# module_led.net
KiCad netlist of a schematic drawn in Altium Designer
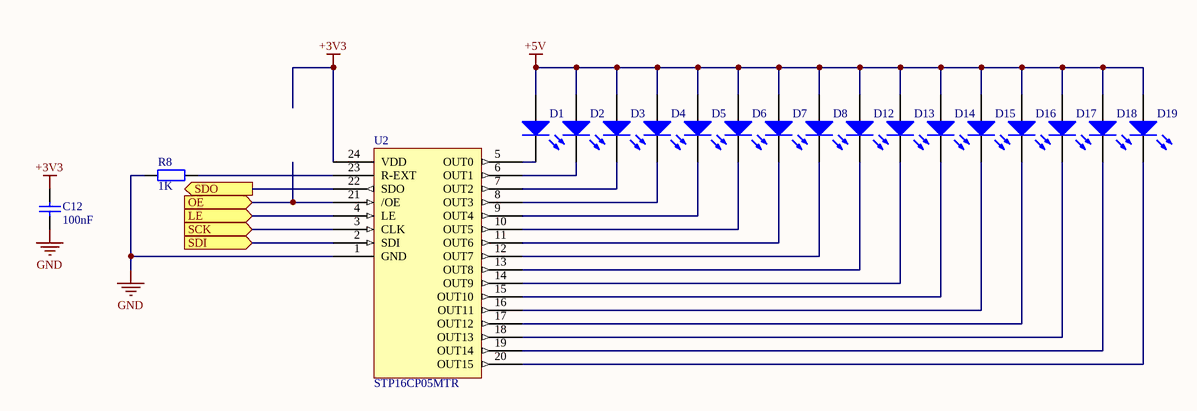
[diagram p0: module_led.SchDoc]

(export (version "E")
  (design (tool "Eeschema 10.0.6"))
  (components
    (comp (ref "C12")
      (value "100nF")
      (footprint "FP_0805_CAP_085")
      (description "Capacitor")
      (fields (field (name "VOLTAGE") "50V"))
      (libsource (lib "hallglib-2018") (part "CAP 100nF"))
    )
    (comp (ref "D1")
      (value "LED")
      (footprint "FP_0805_LED_RED")
      (description "Typical RED GaAs LED")
      (libsource (lib "hallglib") (part "LED"))
    )
    (comp (ref "D2")
      (value "LED")
      (footprint "FP_0805_LED_RED")
      (description "Typical RED GaAs LED")
      (libsource (lib "hallglib") (part "LED"))
    )
    (comp (ref "D3")
      (value "LED")
      (footprint "FP_0805_LED_RED")
      (description "Typical RED GaAs LED")
      (libsource (lib "hallglib") (part "LED"))
    )
    (comp (ref "D4")
      (value "LED")
      (footprint "FP_0805_LED_RED")
      (description "Typical RED GaAs LED")
      (libsource (lib "hallglib") (part "LED"))
    )
    (comp (ref "D5")
      (value "LED")
      (footprint "FP_0805_LED_RED")
      (description "Typical RED GaAs LED")
      (libsource (lib "hallglib") (part "LED"))
    )
    (comp (ref "D6")
      (value "LED")
      (footprint "FP_0805_LED_RED")
      (description "Typical RED GaAs LED")
      (libsource (lib "hallglib") (part "LED"))
    )
    (comp (ref "D7")
      (value "LED")
      (footprint "FP_0805_LED_RED")
      (description "Typical RED GaAs LED")
      (libsource (lib "hallglib") (part "LED"))
    )
    (comp (ref "D8")
      (value "LED")
      (footprint "FP_0805_LED_RED")
      (description "Typical RED GaAs LED")
      (libsource (lib "hallglib") (part "LED"))
    )
    (comp (ref "D12")
      (value "LED")
      (footprint "FP_0805_LED_RED")
      (description "Typical RED GaAs LED")
      (libsource (lib "hallglib") (part "LED"))
    )
    (comp (ref "D13")
      (value "LED")
      (footprint "FP_0805_LED_RED")
      (description "Typical RED GaAs LED")
      (libsource (lib "hallglib") (part "LED"))
    )
    (comp (ref "D14")
      (value "LED")
      (footprint "FP_0805_LED_RED")
      (description "Typical RED GaAs LED")
      (libsource (lib "hallglib") (part "LED"))
    )
    (comp (ref "D15")
      (value "LED")
      (footprint "FP_0805_LED_RED")
      (description "Typical RED GaAs LED")
      (libsource (lib "hallglib") (part "LED"))
    )
    (comp (ref "D16")
      (value "LED")
      (footprint "FP_0805_LED_RED")
      (description "Typical RED GaAs LED")
      (libsource (lib "hallglib") (part "LED"))
    )
    (comp (ref "D17")
      (value "LED")
      (footprint "FP_0805_LED_RED")
      (description "Typical RED GaAs LED")
      (libsource (lib "hallglib") (part "LED"))
    )
    (comp (ref "D18")
      (value "LED")
      (footprint "FP_0805_LED_RED")
      (description "Typical RED GaAs LED")
      (libsource (lib "hallglib") (part "LED"))
    )
    (comp (ref "D19")
      (value "LED")
      (footprint "FP_0805_LED_RED")
      (description "Typical RED GaAs LED")
      (libsource (lib "hallglib") (part "LED"))
    )
    (comp (ref "R8")
      (value "1K")
      (footprint "FP_0805_RES")
      (description "Resistor")
      (fields (field (name "Comment") "R_EL"))
      (libsource (lib "hallglib") (part "RES"))
    )
    (comp (ref "U2")
      (value "STP16CP05MTR")
      (footprint "SOP24")
      (description "LED driver [16]")
      (libsource (lib "mb") (part "STP16CP05MTR"))
    )
  )
  (nets
    (net (code "1") (name "+3V3") (class "Default")
      (node (ref "C12") (pin "2") (pinfunction "2_2") (pintype "passive"))
      (node (ref "U2") (pin "24") (pinfunction "VDD_24") (pintype "passive"))
    )
    (net (code "2") (name "+5V") (class "Default")
      (node (ref "D1") (pin "1") (pinfunction "A_1") (pintype "passive"))
      (node (ref "D12") (pin "1") (pinfunction "A_1") (pintype "passive"))
      (node (ref "D13") (pin "1") (pinfunction "A_1") (pintype "passive"))
      (node (ref "D14") (pin "1") (pinfunction "A_1") (pintype "passive"))
      (node (ref "D15") (pin "1") (pinfunction "A_1") (pintype "passive"))
      (node (ref "D16") (pin "1") (pinfunction "A_1") (pintype "passive"))
      (node (ref "D17") (pin "1") (pinfunction "A_1") (pintype "passive"))
      (node (ref "D18") (pin "1") (pinfunction "A_1") (pintype "passive"))
      (node (ref "D19") (pin "1") (pinfunction "A_1") (pintype "passive"))
      (node (ref "D2") (pin "1") (pinfunction "A_1") (pintype "passive"))
      (node (ref "D3") (pin "1") (pinfunction "A_1") (pintype "passive"))
      (node (ref "D4") (pin "1") (pinfunction "A_1") (pintype "passive"))
      (node (ref "D5") (pin "1") (pinfunction "A_1") (pintype "passive"))
      (node (ref "D6") (pin "1") (pinfunction "A_1") (pintype "passive"))
      (node (ref "D7") (pin "1") (pinfunction "A_1") (pintype "passive"))
      (node (ref "D8") (pin "1") (pinfunction "A_1") (pintype "passive"))
    )
    (net (code "3") (name "/LE") (class "Default")
      (node (ref "U2") (pin "4") (pinfunction "LE_4") (pintype "input"))
    )
    (net (code "4") (name "/OE") (class "Default")
      (node (ref "U2") (pin "21") (pinfunction "/OE_21") (pintype "input"))
    )
    (net (code "5") (name "/SCK") (class "Default")
      (node (ref "U2") (pin "3") (pinfunction "CLK_3") (pintype "input"))
    )
    (net (code "6") (name "/SDI") (class "Default")
      (node (ref "U2") (pin "2") (pinfunction "SDI_2") (pintype "input"))
    )
    (net (code "7") (name "/SDO") (class "Default")
      (node (ref "U2") (pin "22") (pinfunction "SDO_22") (pintype "output"))
    )
    (net (code "8") (name "GND") (class "Default")
      (node (ref "C12") (pin "1") (pinfunction "1_1") (pintype "passive"))
      (node (ref "R8") (pin "2") (pinfunction "2_2") (pintype "passive"))
      (node (ref "U2") (pin "1") (pinfunction "GND_1") (pintype "power_in"))
    )
    (net (code "9") (name "Net-(D1-K)") (class "Default")
      (node (ref "D1") (pin "2") (pinfunction "K_2") (pintype "passive"))
      (node (ref "U2") (pin "5") (pinfunction "OUT0_5") (pintype "output"))
    )
    (net (code "10") (name "Net-(D2-K)") (class "Default")
      (node (ref "D2") (pin "2") (pinfunction "K_2") (pintype "passive"))
      (node (ref "U2") (pin "6") (pinfunction "OUT1_6") (pintype "output"))
    )
    (net (code "11") (name "Net-(D3-K)") (class "Default")
      (node (ref "D3") (pin "2") (pinfunction "K_2") (pintype "passive"))
      (node (ref "U2") (pin "7") (pinfunction "OUT2_7") (pintype "output"))
    )
    (net (code "12") (name "Net-(D4-K)") (class "Default")
      (node (ref "D4") (pin "2") (pinfunction "K_2") (pintype "passive"))
      (node (ref "U2") (pin "8") (pinfunction "OUT3_8") (pintype "output"))
    )
    (net (code "13") (name "Net-(D5-K)") (class "Default")
      (node (ref "D5") (pin "2") (pinfunction "K_2") (pintype "passive"))
      (node (ref "U2") (pin "9") (pinfunction "OUT4_9") (pintype "output"))
    )
    (net (code "14") (name "Net-(D6-K)") (class "Default")
      (node (ref "D6") (pin "2") (pinfunction "K_2") (pintype "passive"))
      (node (ref "U2") (pin "10") (pinfunction "OUT5_10") (pintype "output"))
    )
    (net (code "15") (name "Net-(D7-K)") (class "Default")
      (node (ref "D7") (pin "2") (pinfunction "K_2") (pintype "passive"))
      (node (ref "U2") (pin "11") (pinfunction "OUT6_11") (pintype "output"))
    )
    (net (code "16") (name "Net-(D8-K)") (class "Default")
      (node (ref "D8") (pin "2") (pinfunction "K_2") (pintype "passive"))
      (node (ref "U2") (pin "12") (pinfunction "OUT7_12") (pintype "output"))
    )
    (net (code "17") (name "Net-(D12-K)") (class "Default")
      (node (ref "D12") (pin "2") (pinfunction "K_2") (pintype "passive"))
      (node (ref "U2") (pin "13") (pinfunction "OUT8_13") (pintype "output"))
    )
    (net (code "18") (name "Net-(D13-K)") (class "Default")
      (node (ref "D13") (pin "2") (pinfunction "K_2") (pintype "passive"))
      (node (ref "U2") (pin "14") (pinfunction "OUT9_14") (pintype "output"))
    )
    (net (code "19") (name "Net-(D14-K)") (class "Default")
      (node (ref "D14") (pin "2") (pinfunction "K_2") (pintype "passive"))
      (node (ref "U2") (pin "15") (pinfunction "OUT10_15") (pintype "output"))
    )
    (net (code "20") (name "Net-(D15-K)") (class "Default")
      (node (ref "D15") (pin "2") (pinfunction "K_2") (pintype "passive"))
      (node (ref "U2") (pin "16") (pinfunction "OUT11_16") (pintype "output"))
    )
    (net (code "21") (name "Net-(D16-K)") (class "Default")
      (node (ref "D16") (pin "2") (pinfunction "K_2") (pintype "passive"))
      (node (ref "U2") (pin "17") (pinfunction "OUT12_17") (pintype "output"))
    )
    (net (code "22") (name "Net-(D17-K)") (class "Default")
      (node (ref "D17") (pin "2") (pinfunction "K_2") (pintype "passive"))
      (node (ref "U2") (pin "18") (pinfunction "OUT13_18") (pintype "output"))
    )
    (net (code "23") (name "Net-(D18-K)") (class "Default")
      (node (ref "D18") (pin "2") (pinfunction "K_2") (pintype "passive"))
      (node (ref "U2") (pin "19") (pinfunction "OUT14_19") (pintype "output"))
    )
    (net (code "24") (name "Net-(D19-K)") (class "Default")
      (node (ref "D19") (pin "2") (pinfunction "K_2") (pintype "passive"))
      (node (ref "U2") (pin "20") (pinfunction "OUT15_20") (pintype "output"))
    )
    (net (code "25") (name "Net-(U2-R-EXT)") (class "Default")
      (node (ref "R8") (pin "1") (pinfunction "1_1") (pintype "passive"))
      (node (ref "U2") (pin "23") (pinfunction "R-EXT_23") (pintype "passive"))
    )
  )
)
